# gas-sensor_2021-07-04.net
KiCad netlist of a schematic drawn in EasyEDA
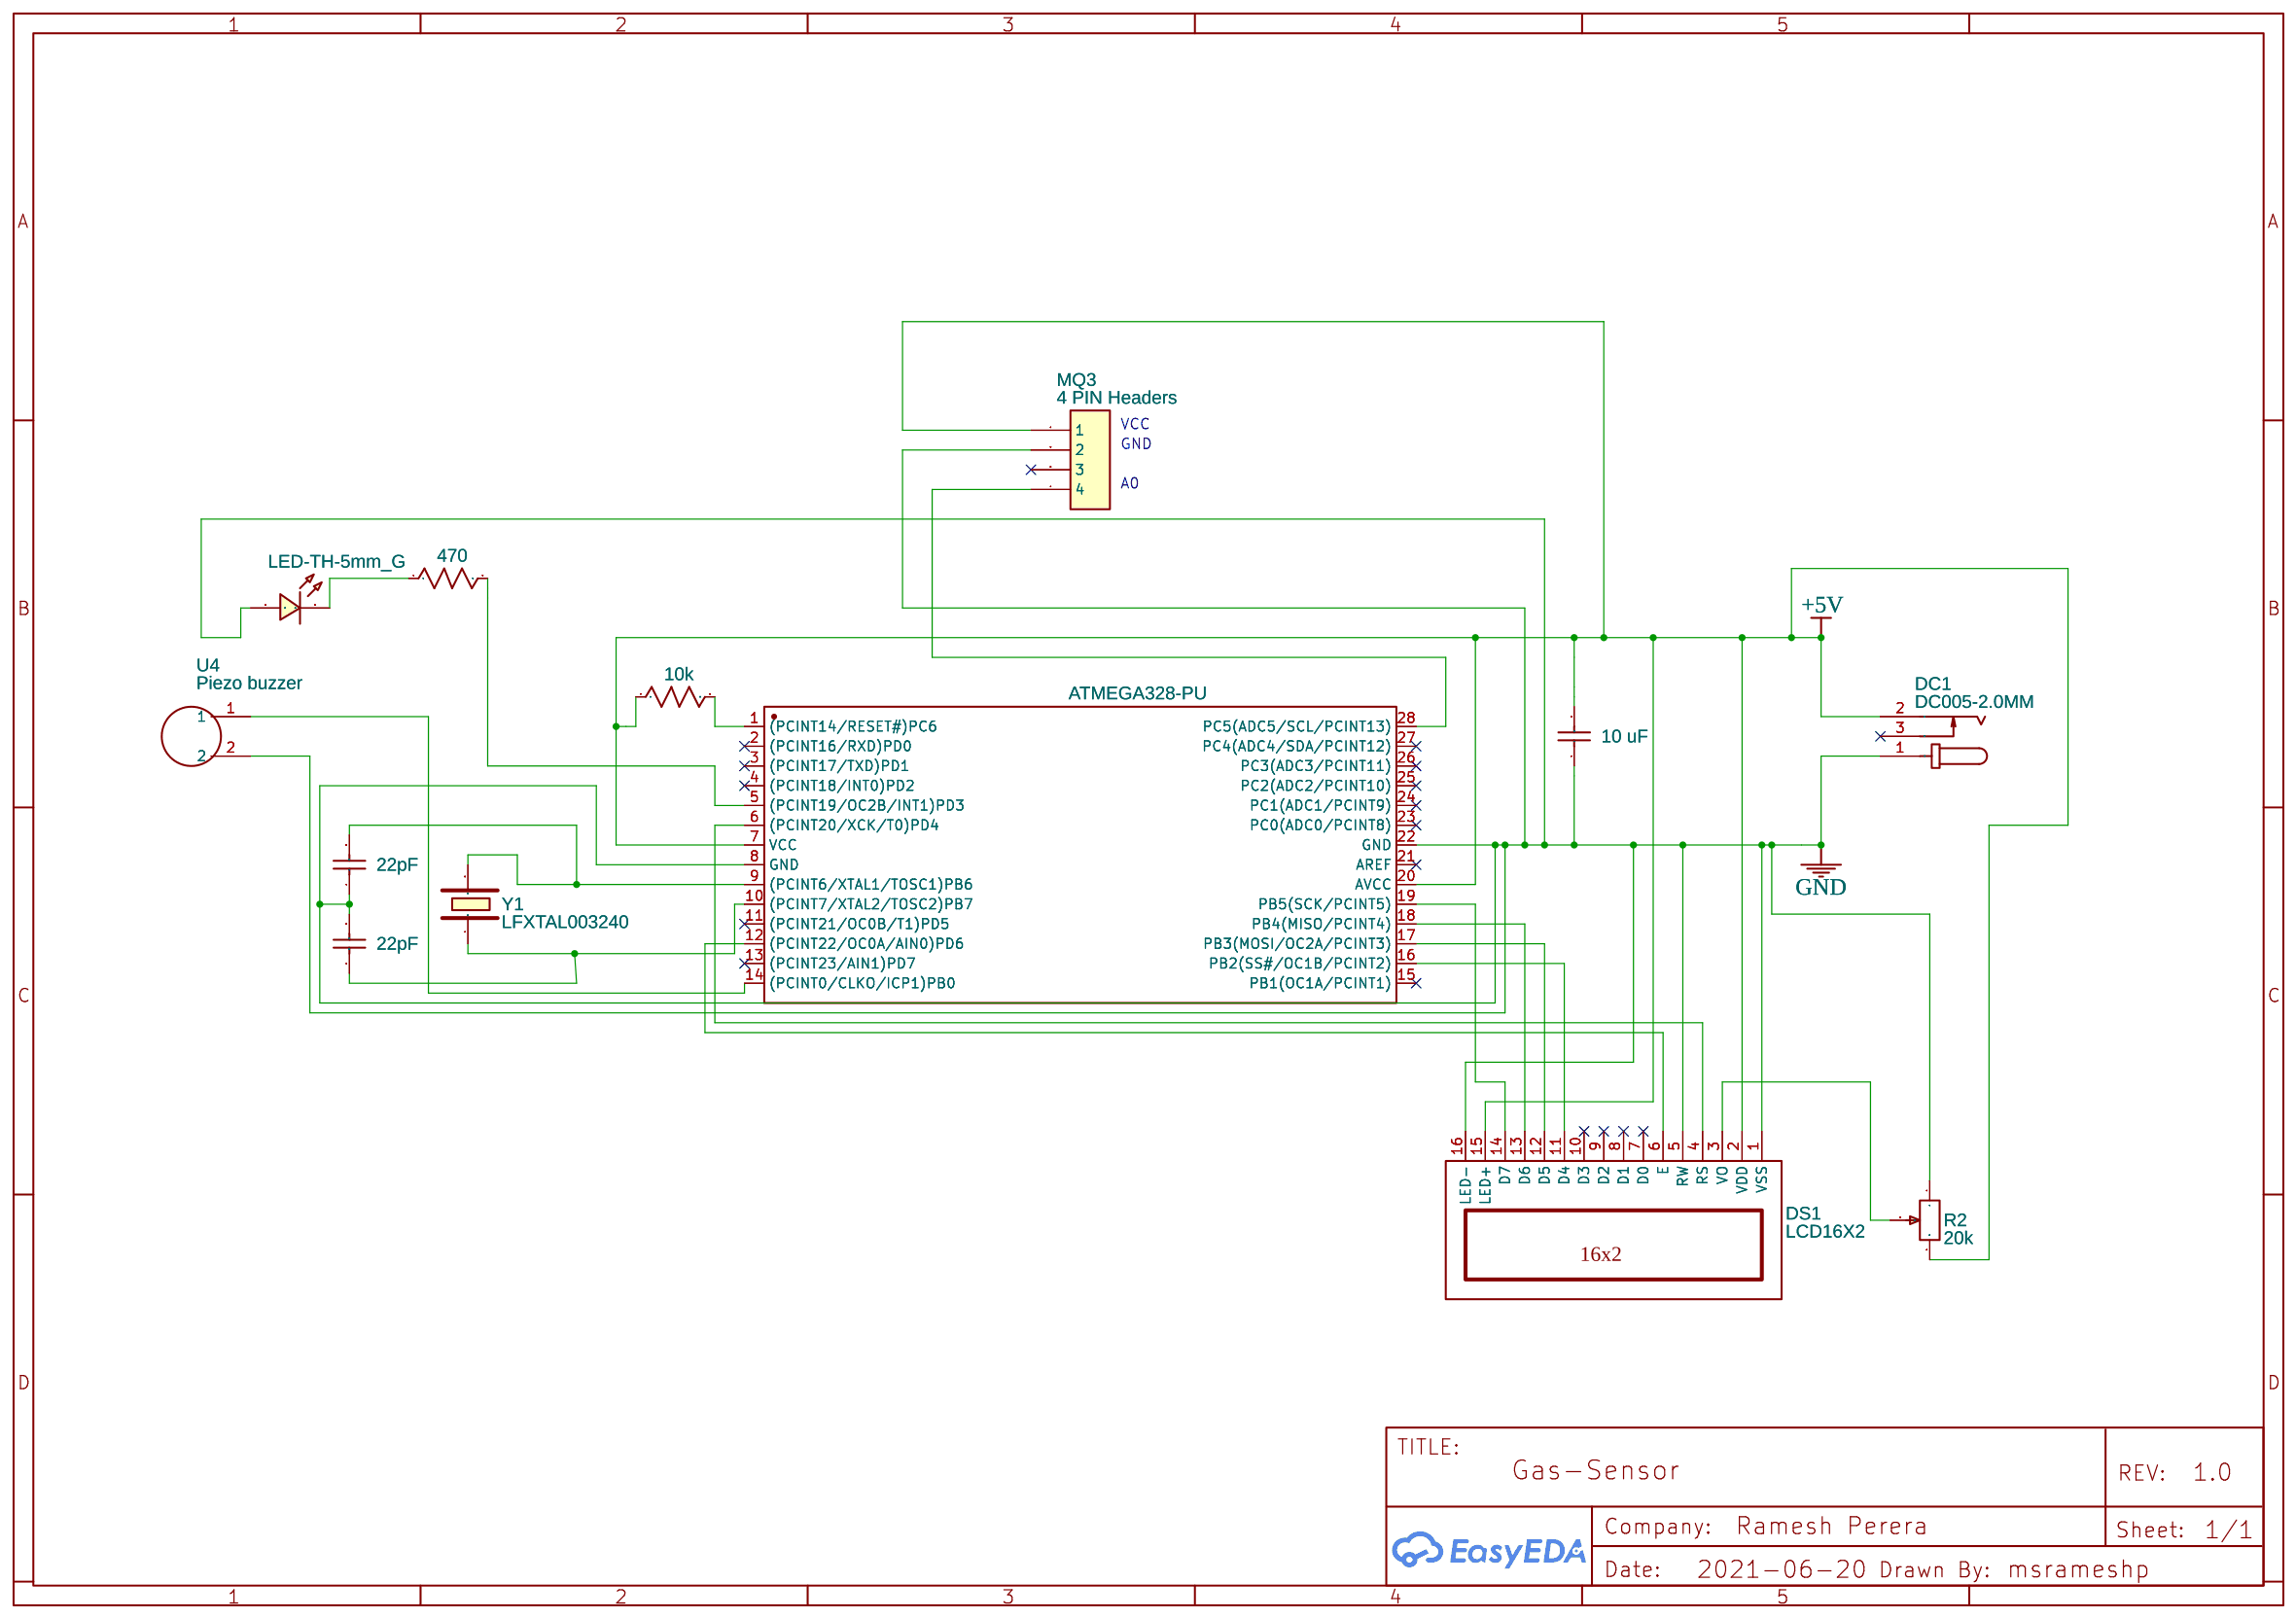
[diagram p0: schematic sheet]

(export (version "E")
  (design (tool "Eeschema 10.0.6"))
  (components
    (comp (ref "C1")
      (value "22pF")
      (fields
        (field (name "BOM_Manufacturer Part") "Ceramic capacitors47PF 3KV")
        (field (name "BOM_Supplier Part") "C19375")
      )
      (libsource (lib "") (part "Ceramic capacitors47PF 3KV"))
    )
    (comp (ref "C2")
      (value "10 uF")
      (fields
        (field (name "BOM_Manufacturer Part") "Ceramic capacitors47PF 3KV")
        (field (name "BOM_Supplier Part") "C19375")
      )
      (libsource (lib "") (part "Ceramic capacitors47PF 3KV"))
    )
    (comp (ref "C4")
      (value "22pF")
      (fields
        (field (name "BOM_Manufacturer Part") "Ceramic capacitors47PF 3KV")
        (field (name "BOM_Supplier Part") "C19375")
      )
      (libsource (lib "") (part "Ceramic capacitors47PF 3KV"))
    )
    (comp (ref "DC1")
      (value "DC005-2.0MM")
      (fields (field (name "BOM_Supplier Part") "C111567"))
      (libsource (lib "") (part "DC005-2.0MM"))
    )
    (comp (ref "DS1") (value "LCD16X2") (libsource (lib "") (part "LCD16X2")))
    (comp (ref "LED1")
      (value "LED-TH-5mm_G")
      (fields
        (field (name "BOM_Manufacturer Part") "333-2SYGD/S530-E2")
        (field (name "BOM_Supplier Part") "C88163")
      )
      (libsource (lib "") (part "LED-TH-5mm_G"))
    )
    (comp (ref "MQ3")
      (value "4 PIN Headers")
      (fields (field (name "BOM_Manufacturer Part") "New SchematicLib"))
      (libsource (lib "") (part "4 PIN Headers"))
    )
    (comp (ref "R2")
      (value "20k")
      (fields
        (field (name "BOM_Manufacturer Part") "3296W-1-104LF")
        (field (name "BOM_Supplier Part") "C118963")
      )
      (libsource (lib "") (part "3296W-1-104LF"))
    )
    (comp (ref "R3") (value "10k") (libsource (lib "") (part "R_AXIAL-0.3_US")))
    (comp (ref "R4") (value "470") (libsource (lib "") (part "R_AXIAL-0.3_US")))
    (comp (ref "U1")
      (value "ATMEGA328-PU")
      (fields (field (name "BOM_Supplier Part") "C613508"))
      (libsource (lib "") (part "ATMEGA328-PU"))
    )
    (comp (ref "U4")
      (value "Piezo buzzer")
      (fields
        (field (name "BOM_Manufacturer Part") "TP124005-2")
        (field (name "BOM_Supplier Part") "2104-TP124005-2CT-ND")
      )
      (libsource (lib "") (part "Piezo buzzer"))
    )
    (comp (ref "Y1")
      (value "LFXTAL003240")
      (fields (field (name "BOM_Supplier Part") "9713700"))
      (libsource (lib "") (part "LFXTAL003240"))
    )
  )
  (nets
    (net (code "1") (name "+5V") (class "Default")
      (node (ref "C2") (pin "2") (pinfunction "2_2") (pintype "input"))
      (node (ref "DC1") (pin "2") (pinfunction "2_2") (pintype "unspecified"))
      (node (ref "DS1") (pin "15") (pinfunction "LED+_15") (pintype "unspecified"))
      (node (ref "DS1") (pin "2") (pinfunction "VDD_2") (pintype "passive"))
      (node (ref "MQ3") (pin "1") (pinfunction "1_1") (pintype "input"))
      (node (ref "R2") (pin "3") (pinfunction "3_3") (pintype "input"))
      (node (ref "R3") (pin "1") (pinfunction "1_1") (pintype "unspecified"))
      (node (ref "U1") (pin "20") (pinfunction "AVCC_20") (pintype "unspecified"))
      (node (ref "U1") (pin "7") (pinfunction "VCC_7") (pintype "unspecified"))
    )
    (net (code "2") (name "GND") (class "Default")
      (node (ref "C1") (pin "2") (pinfunction "2_2") (pintype "input"))
      (node (ref "C2") (pin "1") (pinfunction "1_1") (pintype "input"))
      (node (ref "C4") (pin "1") (pinfunction "1_1") (pintype "input"))
      (node (ref "DC1") (pin "1") (pinfunction "1_1") (pintype "unspecified"))
      (node (ref "DS1") (pin "1") (pinfunction "VSS_1") (pintype "passive"))
      (node (ref "DS1") (pin "16") (pinfunction "LED-_16") (pintype "unspecified"))
      (node (ref "DS1") (pin "5") (pinfunction "RW_5") (pintype "input"))
      (node (ref "LED1") (pin "1") (pinfunction "1_1") (pintype "unspecified"))
      (node (ref "MQ3") (pin "2") (pinfunction "2_2") (pintype "input"))
      (node (ref "R2") (pin "1") (pinfunction "1_1") (pintype "input"))
      (node (ref "U1") (pin "22") (pinfunction "GND_22") (pintype "unspecified"))
      (node (ref "U1") (pin "8") (pinfunction "GND_8") (pintype "unspecified"))
      (node (ref "U4") (pin "2") (pinfunction "2_2") (pintype "unspecified"))
    )
    (net (code "3") (name "Net-(DS1-D4)") (class "Default")
      (node (ref "DS1") (pin "11") (pinfunction "D4_11") (pintype "input"))
      (node (ref "U1") (pin "16") (pinfunction "PB2(SS#/OC1B/PCINT2)_16") (pintype "unspecified"))
    )
    (net (code "4") (name "Net-(DS1-D5)") (class "Default")
      (node (ref "DS1") (pin "12") (pinfunction "D5_12") (pintype "input"))
      (node (ref "U1") (pin "17") (pinfunction "PB3(MOSI/OC2A/PCINT3)_17") (pintype "unspecified"))
    )
    (net (code "5") (name "Net-(DS1-D6)") (class "Default")
      (node (ref "DS1") (pin "13") (pinfunction "D6_13") (pintype "input"))
      (node (ref "U1") (pin "18") (pinfunction "PB4(MISO/PCINT4)_18") (pintype "unspecified"))
    )
    (net (code "6") (name "Net-(DS1-D7)") (class "Default")
      (node (ref "DS1") (pin "14") (pinfunction "D7_14") (pintype "input"))
      (node (ref "U1") (pin "19") (pinfunction "PB5(SCK/PCINT5)_19") (pintype "unspecified"))
    )
    (net (code "7") (name "Net-(DS1-E)") (class "Default")
      (node (ref "DS1") (pin "6") (pinfunction "E_6") (pintype "input"))
      (node (ref "U1") (pin "12") (pinfunction "(PCINT22/OC0A/AIN0)PD6_12") (pintype "unspecified"))
    )
    (net (code "8") (name "Net-(DS1-RS)") (class "Default")
      (node (ref "DS1") (pin "4") (pinfunction "RS_4") (pintype "input"))
      (node (ref "U1") (pin "6") (pinfunction "(PCINT20/XCK/T0)PD4_6") (pintype "unspecified"))
    )
    (net (code "9") (name "Net-(DS1-VO)") (class "Default")
      (node (ref "DS1") (pin "3") (pinfunction "VO_3") (pintype "input"))
      (node (ref "R2") (pin "2") (pinfunction "2_2") (pintype "input"))
    )
    (net (code "10") (name "Net-(LED1-Pad2)") (class "Default")
      (node (ref "LED1") (pin "2") (pinfunction "2_2") (pintype "unspecified"))
      (node (ref "R4") (pin "1") (pinfunction "1_1") (pintype "unspecified"))
    )
    (net (code "11") (name "Net-(U1-(PCINT0{slash}CLKO{slash}ICP1)PB0)") (class "Default")
      (node (ref "U1") (pin "14") (pinfunction "(PCINT0/CLKO/ICP1)PB0_14") (pintype "unspecified"))
      (node (ref "U4") (pin "1") (pinfunction "1_1") (pintype "unspecified"))
    )
    (net (code "12") (name "Net-(U1-(PCINT6{slash}XTAL1{slash}TOSC1)PB6)") (class "Default")
      (node (ref "C4") (pin "2") (pinfunction "2_2") (pintype "input"))
      (node (ref "U1") (pin "9") (pinfunction "(PCINT6/XTAL1/TOSC1)PB6_9") (pintype "unspecified"))
      (node (ref "Y1") (pin "2") (pinfunction "2_2") (pintype "unspecified"))
    )
    (net (code "13") (name "Net-(U1-(PCINT7{slash}XTAL2{slash}TOSC2)PB7)") (class "Default")
      (node (ref "C1") (pin "1") (pinfunction "1_1") (pintype "input"))
      (node (ref "U1") (pin "10") (pinfunction "(PCINT7/XTAL2/TOSC2)PB7_10") (pintype "unspecified"))
      (node (ref "Y1") (pin "1") (pinfunction "1_1") (pintype "unspecified"))
    )
    (net (code "14") (name "Net-(U1-(PCINT14{slash}RESET#)PC6)") (class "Default")
      (node (ref "R3") (pin "2") (pinfunction "2_2") (pintype "unspecified"))
      (node (ref "U1") (pin "1") (pinfunction "(PCINT14/RESET#)PC6_1") (pintype "unspecified"))
    )
    (net (code "15") (name "Net-(U1-(PCINT19{slash}OC2B{slash}INT1)PD3)") (class "Default")
      (node (ref "R4") (pin "2") (pinfunction "2_2") (pintype "unspecified"))
      (node (ref "U1") (pin "5") (pinfunction "(PCINT19/OC2B/INT1)PD3_5") (pintype "unspecified"))
    )
    (net (code "16") (name "Net-(U1-PC5(ADC5{slash}SCL{slash}PCINT13))") (class "Default")
      (node (ref "MQ3") (pin "4") (pinfunction "4_4") (pintype "input"))
      (node (ref "U1") (pin "28") (pinfunction "PC5(ADC5/SCL/PCINT13)_28") (pintype "unspecified"))
    )
    (net (code "17") (name "unconnected-(DC1-Pad3)") (class "Default")
      (node (ref "DC1") (pin "3") (pinfunction "3_3") (pintype "unspecified+no_connect"))
    )
    (net (code "18") (name "unconnected-(DS1-D0-Pad7)") (class "Default")
      (node (ref "DS1") (pin "7") (pinfunction "D0_7") (pintype "input+no_connect"))
    )
    (net (code "19") (name "unconnected-(DS1-D1-Pad8)") (class "Default")
      (node (ref "DS1") (pin "8") (pinfunction "D1_8") (pintype "input+no_connect"))
    )
    (net (code "20") (name "unconnected-(DS1-D2-Pad9)") (class "Default")
      (node (ref "DS1") (pin "9") (pinfunction "D2_9") (pintype "input+no_connect"))
    )
    (net (code "21") (name "unconnected-(DS1-D3-Pad10)") (class "Default")
      (node (ref "DS1") (pin "10") (pinfunction "D3_10") (pintype "input+no_connect"))
    )
    (net (code "22") (name "unconnected-(MQ3-Pad3)") (class "Default")
      (node (ref "MQ3") (pin "3") (pinfunction "3_3") (pintype "input+no_connect"))
    )
    (net (code "23") (name "unconnected-(U1-(PCINT16{slash}RXD)PD0-Pad2)") (class "Default")
      (node (ref "U1") (pin "2") (pinfunction "(PCINT16/RXD)PD0_2") (pintype "unspecified+no_connect"))
    )
    (net (code "24") (name "unconnected-(U1-(PCINT17{slash}TXD)PD1-Pad3)") (class "Default")
      (node (ref "U1") (pin "3") (pinfunction "(PCINT17/TXD)PD1_3") (pintype "unspecified+no_connect"))
    )
    (net (code "25") (name "unconnected-(U1-(PCINT18{slash}INT0)PD2-Pad4)") (class "Default")
      (node (ref "U1") (pin "4") (pinfunction "(PCINT18/INT0)PD2_4") (pintype "unspecified+no_connect"))
    )
    (net (code "26") (name "unconnected-(U1-(PCINT21{slash}OC0B{slash}T1)PD5-Pad11)") (class "Default")
      (node (ref "U1") (pin "11") (pinfunction "(PCINT21/OC0B/T1)PD5_11") (pintype "unspecified+no_connect"))
    )
    (net (code "27") (name "unconnected-(U1-(PCINT23{slash}AIN1)PD7-Pad13)") (class "Default")
      (node (ref "U1") (pin "13") (pinfunction "(PCINT23/AIN1)PD7_13") (pintype "unspecified+no_connect"))
    )
    (net (code "28") (name "unconnected-(U1-AREF-Pad21)") (class "Default")
      (node (ref "U1") (pin "21") (pinfunction "AREF_21") (pintype "unspecified+no_connect"))
    )
    (net (code "29") (name "unconnected-(U1-PB1(OC1A{slash}PCINT1)-Pad15)") (class "Default")
      (node (ref "U1") (pin "15") (pinfunction "PB1(OC1A/PCINT1)_15") (pintype "unspecified+no_connect"))
    )
    (net (code "30") (name "unconnected-(U1-PC0(ADC0{slash}PCINT8)-Pad23)") (class "Default")
      (node (ref "U1") (pin "23") (pinfunction "PC0(ADC0/PCINT8)_23") (pintype "unspecified+no_connect"))
    )
    (net (code "31") (name "unconnected-(U1-PC1(ADC1{slash}PCINT9)-Pad24)") (class "Default")
      (node (ref "U1") (pin "24") (pinfunction "PC1(ADC1/PCINT9)_24") (pintype "unspecified+no_connect"))
    )
    (net (code "32") (name "unconnected-(U1-PC2(ADC2{slash}PCINT10)-Pad25)") (class "Default")
      (node (ref "U1") (pin "25") (pinfunction "PC2(ADC2/PCINT10)_25") (pintype "unspecified+no_connect"))
    )
    (net (code "33") (name "unconnected-(U1-PC3(ADC3{slash}PCINT11)-Pad26)") (class "Default")
      (node (ref "U1") (pin "26") (pinfunction "PC3(ADC3/PCINT11)_26") (pintype "unspecified+no_connect"))
    )
    (net (code "34") (name "unconnected-(U1-PC4(ADC4{slash}SDA{slash}PCINT12)-Pad27)") (class "Default")
      (node (ref "U1") (pin "27") (pinfunction "PC4(ADC4/SDA/PCINT12)_27") (pintype "unspecified+no_connect"))
    )
  )
)
